# untitled.net
KiCad netlist of a schematic drawn in EAGLE
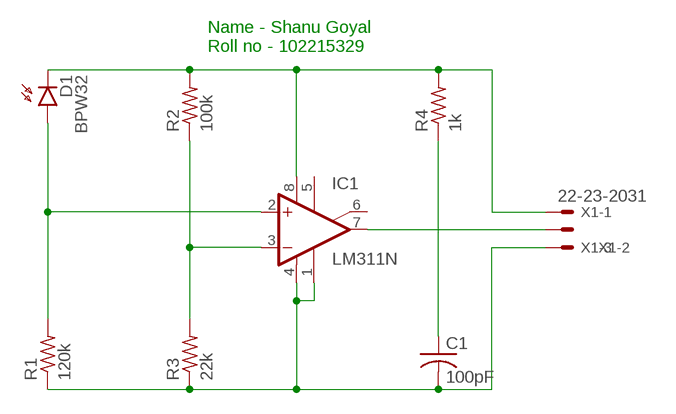
[diagram p0: schematic, sheet 1]

(export (version "E")
  (design (tool "Eeschema 10.0.6"))
  (components
    (comp (ref "C1")
      (value "100pF")
      (footprint "eagle-import:C025-050X050")
      (libsource (lib "eagle-import") (part "C-US025-050X050"))
    )
    (comp (ref "D1")
      (value "BPW32")
      (footprint "eagle-import:BPW32")
      (libsource (lib "eagle-import") (part "BPW32"))
    )
    (comp (ref "IC1")
      (value "LM311N")
      (footprint "eagle-import:DIL08")
      (libsource (lib "eagle-import") (part "LM311N"))
    )
    (comp (ref "R1")
      (value "120k")
      (footprint "eagle-import:0204_5")
      (libsource (lib "eagle-import") (part "R-US_0204/5"))
    )
    (comp (ref "R2")
      (value "100k")
      (footprint "eagle-import:0204_5")
      (libsource (lib "eagle-import") (part "R-US_0204/5"))
    )
    (comp (ref "R3")
      (value "22k")
      (footprint "eagle-import:0204_5")
      (libsource (lib "eagle-import") (part "R-US_0204/5"))
    )
    (comp (ref "R4")
      (value "1k")
      (footprint "eagle-import:0204_5")
      (libsource (lib "eagle-import") (part "R-US_0204/5"))
    )
    (comp (ref "X1")
      (value "22-23-2031")
      (footprint "eagle-import:22-23-2031")
      (fields (field (name "MF") "MOLEX"))
      (libsource (lib "eagle-import") (part "22-23-2031"))
    )
  )
  (nets
    (net (code "1") (name "Net-(C1-Pad1)") (class "Default")
      (node (ref "C1") (pin "1") (pinfunction "1_1") (pintype "passive"))
      (node (ref "R4") (pin "1") (pinfunction "1_1") (pintype "passive"))
    )
    (net (code "2") (name "Net-(D1-C)") (class "Default")
      (node (ref "D1") (pin "K") (pinfunction "C_K") (pintype "passive"))
      (node (ref "IC1") (pin "8") (pinfunction "V+_8") (pintype "power_in"))
      (node (ref "R2") (pin "2") (pinfunction "2_2") (pintype "passive"))
      (node (ref "R4") (pin "2") (pinfunction "2_2") (pintype "passive"))
      (node (ref "X1") (pin "1") (pinfunction "S_1") (pintype "passive"))
    )
    (net (code "3") (name "Net-(IC1-+IN)") (class "Default")
      (node (ref "D1") (pin "A") (pinfunction "A_A") (pintype "passive"))
      (node (ref "IC1") (pin "2") (pinfunction "+IN_2") (pintype "input"))
      (node (ref "R1") (pin "2") (pinfunction "2_2") (pintype "passive"))
    )
    (net (code "4") (name "Net-(IC1--IN)") (class "Default")
      (node (ref "IC1") (pin "3") (pinfunction "-IN_3") (pintype "input"))
      (node (ref "R2") (pin "1") (pinfunction "1_1") (pintype "passive"))
      (node (ref "R3") (pin "2") (pinfunction "2_2") (pintype "passive"))
    )
    (net (code "5") (name "Net-(IC1-GND)") (class "Default")
      (node (ref "C1") (pin "2") (pinfunction "2_2") (pintype "passive"))
      (node (ref "IC1") (pin "1") (pinfunction "GND_1") (pintype "passive"))
      (node (ref "IC1") (pin "4") (pinfunction "V-_4") (pintype "power_in"))
      (node (ref "R1") (pin "1") (pinfunction "1_1") (pintype "passive"))
      (node (ref "R3") (pin "1") (pinfunction "1_1") (pintype "passive"))
      (node (ref "X1") (pin "3") (pinfunction "S_3") (pintype "passive"))
    )
    (net (code "6") (name "Net-(IC1-OUT)") (class "Default")
      (node (ref "IC1") (pin "7") (pinfunction "OUT_7") (pintype "output"))
      (node (ref "X1") (pin "2") (pinfunction "S_2") (pintype "passive"))
    )
    (net (code "7") (name "unconnected-(IC1-ON-Pad5)") (class "Default")
      (node (ref "IC1") (pin "5") (pinfunction "ON_5") (pintype "passive"))
    )
    (net (code "8") (name "unconnected-(IC1-ON{slash}STR-Pad6)") (class "Default")
      (node (ref "IC1") (pin "6") (pinfunction "ON/STR_6") (pintype "passive"))
    )
  )
)
